# Battery_Chager_x3.net
KiCad netlist of a schematic drawn in Altium Designer
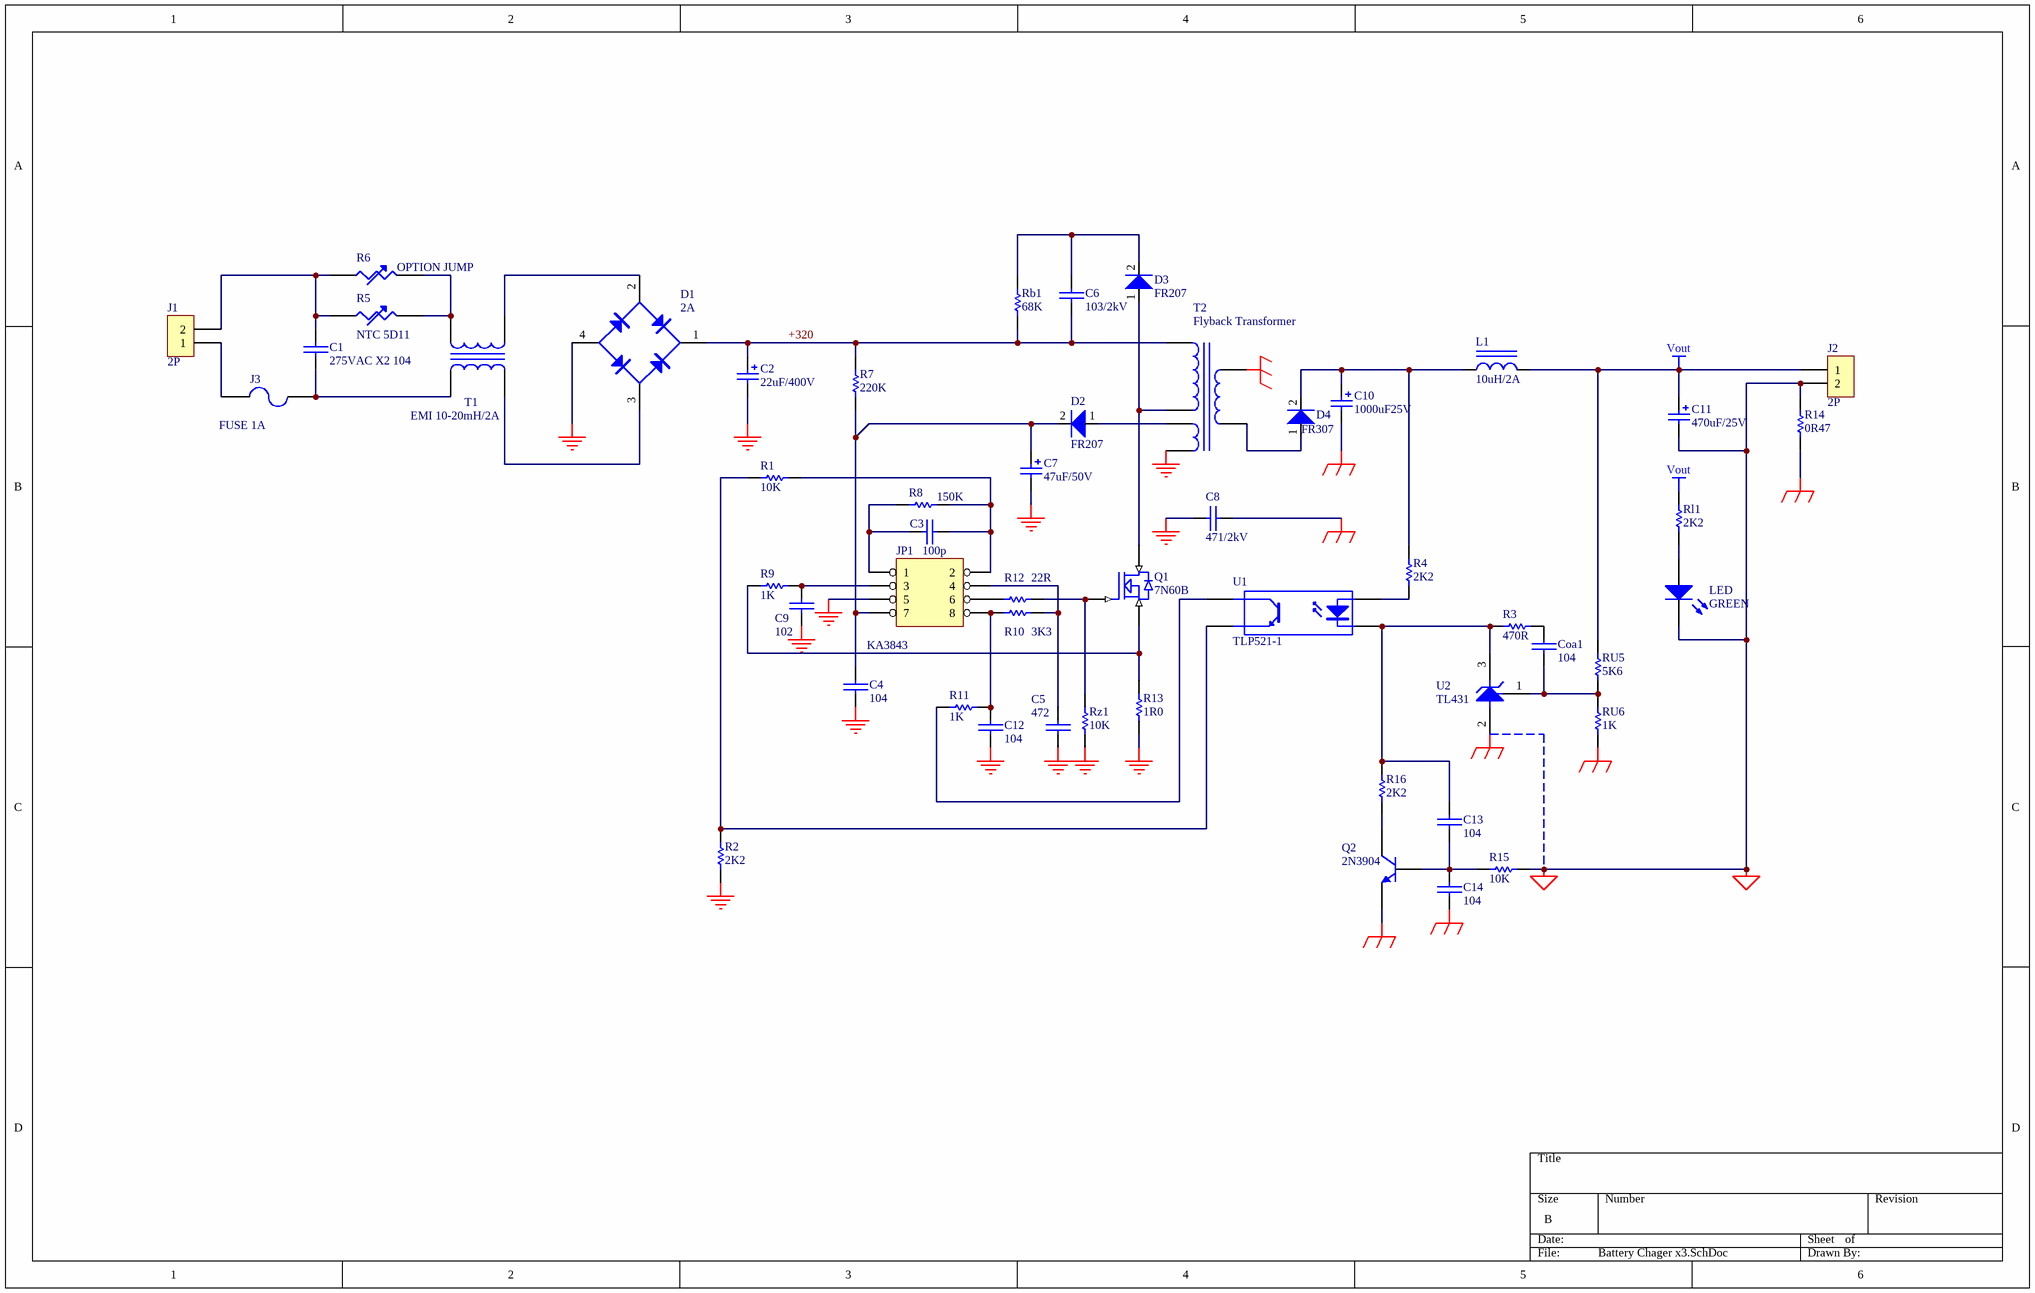
[diagram p0: Battery Chager x3.SchDoc]

(export (version "E")
  (design (tool "Eeschema 10.0.6"))
  (components
    (comp (ref "C1")
      (value "275VAC X2 104")
      (footprint "100N400v")
      (fields (field (name "Comment") "Tụ điện chân cắm275VAC X2 104"))
      (libsource (lib "DnsSchLib") (part "CAP"))
    )
    (comp (ref "C2")
      (value "22uF/400V")
      (footprint "1000u50v")
      (description "Polarized Capacitor (Radial)")
      (fields (field (name "Comment") "Tụ hóa chân cắm22uF/400V") (field (name "PUBLISHER") "*"))
      (libsource (lib "DnsSchLib") (part "Cap Pol1"))
    )
    (comp (ref "C3")
      (value "100p")
      (footprint "0805C")
      (fields (field (name "Comment") "Tụ điện dán 0805100p"))
      (libsource (lib "DnsSchLib") (part "CAP"))
    )
    (comp (ref "C4")
      (value "104")
      (footprint "0805C")
      (fields (field (name "Comment") "Tụ điện dán 0805104"))
      (libsource (lib "DnsSchLib") (part "CAP"))
    )
    (comp (ref "C5")
      (value "472")
      (footprint "104nho")
      (fields (field (name "Comment") "Tụ điện chân cắm472"))
      (libsource (lib "DnsSchLib") (part "CAP"))
    )
    (comp (ref "C6")
      (value "103/2kV")
      (footprint "10n1000v")
      (fields (field (name "Comment") "Tụ điện chân cắm103/2kV"))
      (libsource (lib "DnsSchLib") (part "CAP"))
    )
    (comp (ref "C7")
      (value "47uF/50V")
      (footprint "10u50V")
      (description "Polarized Capacitor (Radial)")
      (fields (field (name "Comment") "Tụ hóa chân cắm47uF/50V") (field (name "PUBLISHER") "*"))
      (libsource (lib "DnsSchLib") (part "Cap Pol1"))
    )
    (comp (ref "C8")
      (value "471/2kV")
      (footprint "10n1000v")
      (fields (field (name "Comment") "Tụ điện chân cắm471/2kV"))
      (libsource (lib "DnsSchLib") (part "CAP"))
    )
    (comp (ref "C9")
      (value "102")
      (footprint "0805C")
      (fields (field (name "Comment") "Tụ điện dán 0805102"))
      (libsource (lib "DnsSchLib") (part "CAP"))
    )
    (comp (ref "C10")
      (value "1000uF25V")
      (footprint "1000u16v")
      (description "Polarized Capacitor (Radial)")
      (fields (field (name "Comment") "Tụ hóa chân cắm1000uF25V") (field (name "PUBLISHER") "*"))
      (libsource (lib "DnsSchLib") (part "Cap Pol1"))
    )
    (comp (ref "C11")
      (value "470uF/25V")
      (footprint "1000u16v")
      (description "Polarized Capacitor (Radial)")
      (fields (field (name "Comment") "Tụ hóa chân cắm470uF/25V") (field (name "PUBLISHER") "*"))
      (libsource (lib "DnsSchLib") (part "Cap Pol1"))
    )
    (comp (ref "C12")
      (value "104")
      (footprint "0805C")
      (fields (field (name "Comment") "Tụ điện dán 0805104"))
      (libsource (lib "DnsSchLib") (part "CAP"))
    )
    (comp (ref "C13")
      (value "104")
      (footprint "0805C")
      (fields (field (name "Comment") "Tụ điện dán 0805104"))
      (libsource (lib "DnsSchLib") (part "CAP"))
    )
    (comp (ref "C14")
      (value "104")
      (footprint "0805C")
      (fields (field (name "Comment") "Tụ điện dán 0805104"))
      (libsource (lib "DnsSchLib") (part "CAP"))
    )
    (comp (ref "Coa1")
      (value "104")
      (footprint "0805C")
      (fields (field (name "Comment") "Tụ điện dán 0805104"))
      (libsource (lib "DnsSchLib") (part "CAP"))
    )
    (comp (ref "D1")
      (value "2A")
      (footprint "Cau2a")
      (description "Diode Bridge")
      (fields (field (name "Comment") "Cầu chỉnh lưu Diode dẹt, chân cắm2A"))
      (libsource (lib "DnsSchLib") (part "BRIDGE1"))
    )
    (comp (ref "D2")
      (value "FR207")
      (footprint "DIODE1A")
      (fields (field (name "Comment") "Diode xung chân cắm 2AFR207"))
      (libsource (lib "DnsSchLib") (part "DIODE"))
    )
    (comp (ref "D3")
      (value "FR207")
      (footprint "DIODE1A")
      (fields (field (name "Comment") "Diode xung chân cắm 2AFR207"))
      (libsource (lib "DnsSchLib") (part "DIODE"))
    )
    (comp (ref "D4")
      (value "FR307")
      (footprint "1N5408")
      (fields (field (name "Comment") "Diode xung chân cắm 3AFR307"))
      (libsource (lib "DnsSchLib") (part "DIODE"))
    )
    (comp (ref "J1")
      (value "2P")
      (footprint "jack2_nam")
      (fields (field (name "Comment") "Jump đực loại thẳng, 2.54mm2P"))
      (libsource (lib "DnsSchLib") (part "CON2"))
    )
    (comp (ref "J2")
      (value "2P")
      (footprint "jack2_nam")
      (fields (field (name "Comment") "Jump đực loại thẳng, 2.54mm2P"))
      (libsource (lib "") (part "CON2_1"))
    )
    (comp (ref "J3")
      (value "FUSE 1A")
      (footprint "R2W_DUNG")
      (description "Fuse")
      (fields (field (name "Comment") "Cầu chì 1A/275V"))
      (libsource (lib "*") (part "FUSE2"))
    )
    (comp (ref "JP1")
      (value "KA3843")
      (footprint "DIP8")
      (fields (field (name "Comment") "IC điều khiển nguồn AC-DC KA3843"))
      (libsource (lib "*") (part "HEADER 4X2"))
    )
    (comp (ref "L1")
      (value "10uH/2A")
      (footprint "330uH")
      (fields (field (name "Comment") "Cuộn cảm chân cắm lõi trụ10uH/2A"))
      (libsource (lib "DnsSchLib") (part "INDUCTORSMALL"))
    )
    (comp (ref "LED")
      (value "GREEN")
      (footprint "LED0805")
      (description "Typical INFRARED GaAs LED")
      (fields (field (name "Comment") "LED dán 0805GREEN") (field (name "PUBLISHER") "*"))
      (libsource (lib "DnsSchLib") (part "LED0"))
    )
    (comp (ref "Q1")
      (value "7N60B")
      (footprint "TO220TNB")
      (fields (field (name "Comment") "Transistor trường MOSFET N, chân cắm TO-2207N60B"))
      (libsource (lib "DnsSchLib") (part "MOSFET N"))
    )
    (comp (ref "Q2")
      (value "2N3904")
      (footprint "SOT23S")
      (description "NPN Bipolar Transistor")
      (fields
        (field (name "Comment") "Transistor BJT NPN, chân dán SOT-232N3904")
        (field (name "PUBLISHER") "*")
      )
      (libsource (lib "DnsSchLib") (part "NPN"))
    )
    (comp (ref "R1")
      (value "10K")
      (footprint "0805DD")
      (description "Semiconductor Resistor")
      (fields (field (name "Comment") "Điện trở dán 080510K") (field (name "PUBLISHER") "*"))
      (libsource (lib "DnsSchLib") (part "Res Semi"))
    )
    (comp (ref "R2")
      (value "2K2")
      (footprint "0805DD")
      (description "Semiconductor Resistor")
      (fields (field (name "Comment") "Điện trở dán 08052K2") (field (name "PUBLISHER") "*"))
      (libsource (lib "DnsSchLib") (part "Res Semi"))
    )
    (comp (ref "R3")
      (value "470R")
      (footprint "0805DD")
      (description "Semiconductor Resistor")
      (fields (field (name "Comment") "Điện trở dán 0805470R") (field (name "PUBLISHER") "*"))
      (libsource (lib "DnsSchLib") (part "Res Semi"))
    )
    (comp (ref "R4")
      (value "2K2")
      (footprint "0805DD")
      (description "Semiconductor Resistor")
      (fields (field (name "Comment") "Điện trở dán 08052K2") (field (name "PUBLISHER") "*"))
      (libsource (lib "DnsSchLib") (part "Res Semi"))
    )
    (comp (ref "R5")
      (value "NTC 5D11")
      (footprint "CSIP4")
      (fields (field (name "Comment") "Nhiệt điện trở âm NTC 5D11"))
      (libsource (lib "*") (part "RES3"))
    )
    (comp (ref "R6") (value "OPTION JUMP") (footprint "XPAD") (libsource (lib "*") (part "RES3")))
    (comp (ref "R7")
      (value "220K")
      (footprint "R2W_DUNG")
      (description "Semiconductor Resistor")
      (fields (field (name "Comment") "Điện trở chân cắm 2W220K") (field (name "PUBLISHER") "*"))
      (libsource (lib "DnsSchLib") (part "Res Semi"))
    )
    (comp (ref "R8")
      (value "150K")
      (footprint "0805DD")
      (description "Semiconductor Resistor")
      (fields (field (name "Comment") "Điện trở dán 0805150K") (field (name "PUBLISHER") "*"))
      (libsource (lib "DnsSchLib") (part "Res Semi"))
    )
    (comp (ref "R9")
      (value "1K")
      (footprint "0805DD")
      (description "Semiconductor Resistor")
      (fields (field (name "Comment") "Điện trở dán 08051K") (field (name "PUBLISHER") "*"))
      (libsource (lib "DnsSchLib") (part "Res Semi"))
    )
    (comp (ref "R10")
      (value "3K3")
      (footprint "0805DD")
      (description "Semiconductor Resistor")
      (fields (field (name "Comment") "Điện trở dán 08053K3") (field (name "PUBLISHER") "*"))
      (libsource (lib "DnsSchLib") (part "Res Semi"))
    )
    (comp (ref "R11")
      (value "1K")
      (footprint "0805DD")
      (description "Semiconductor Resistor")
      (fields (field (name "Comment") "Điện trở dán 08051K") (field (name "PUBLISHER") "*"))
      (libsource (lib "DnsSchLib") (part "Res Semi"))
    )
    (comp (ref "R12")
      (value "22R")
      (footprint "0805DD")
      (description "Semiconductor Resistor")
      (fields (field (name "Comment") "Điện trở dán 080522R") (field (name "PUBLISHER") "*"))
      (libsource (lib "DnsSchLib") (part "Res Semi"))
    )
    (comp (ref "R13")
      (value "1R0")
      (footprint "R2WDUNG")
      (description "Semiconductor Resistor")
      (fields (field (name "Comment") "Điện trở chân cắm 2W1R0") (field (name "PUBLISHER") "*"))
      (libsource (lib "DnsSchLib") (part "Res Semi"))
    )
    (comp (ref "R14")
      (value "0R47")
      (footprint "R2WDUNG")
      (description "Semiconductor Resistor")
      (fields (field (name "Comment") "Điện trở chân cắm 2W0R47") (field (name "PUBLISHER") "*"))
      (libsource (lib "DnsSchLib") (part "Res Semi"))
    )
    (comp (ref "R15")
      (value "10K")
      (footprint "0805DD")
      (description "Semiconductor Resistor")
      (fields (field (name "Comment") "Điện trở dán 080510K") (field (name "PUBLISHER") "*"))
      (libsource (lib "DnsSchLib") (part "Res Semi"))
    )
    (comp (ref "R16")
      (value "2K2")
      (footprint "0805DD")
      (description "Semiconductor Resistor")
      (fields (field (name "Comment") "Điện trở dán 08052K2") (field (name "PUBLISHER") "*"))
      (libsource (lib "DnsSchLib") (part "Res Semi"))
    )
    (comp (ref "Rb1")
      (value "68K")
      (footprint "AXIAL0.4")
      (description "Semiconductor Resistor")
      (fields (field (name "Comment") "Điện trở chân cắm 1W68K") (field (name "PUBLISHER") "*"))
      (libsource (lib "DnsSchLib") (part "Res Semi"))
    )
    (comp (ref "Rl1")
      (value "2K2")
      (footprint "0805DD")
      (description "Semiconductor Resistor")
      (fields (field (name "Comment") "Điện trở dán 08052K2") (field (name "PUBLISHER") "*"))
      (libsource (lib "DnsSchLib") (part "Res Semi"))
    )
    (comp (ref "RU5")
      (value "5K6")
      (footprint "0805DD")
      (description "Semiconductor Resistor")
      (fields (field (name "Comment") "Điện trở dán 08055K6") (field (name "PUBLISHER") "*"))
      (libsource (lib "DnsSchLib") (part "Res Semi"))
    )
    (comp (ref "RU6")
      (value "1K")
      (footprint "0805DD")
      (description "Semiconductor Resistor")
      (fields (field (name "Comment") "Điện trở dán 08051K") (field (name "PUBLISHER") "*"))
      (libsource (lib "DnsSchLib") (part "Res Semi"))
    )
    (comp (ref "Rz1")
      (value "10K")
      (footprint "0805DD")
      (description "Semiconductor Resistor")
      (fields (field (name "Comment") "Điện trở dán 080510K") (field (name "PUBLISHER") "*"))
      (libsource (lib "DnsSchLib") (part "Res Semi"))
    )
    (comp (ref "T1")
      (value "EMI 10-20mH/2A")
      (footprint "EMI_Filter")
      (fields (field (name "Comment") "Cuộn cảm lọc đầu vào EMI Filter 10-20mH/2A"))
      (libsource (lib "*") (part "TRANS1"))
    )
    (comp (ref "T2")
      (value "Flyback Transformer")
      (footprint "Trans6c")
      (fields (field (name "Comment") "Biến áp xung Flyback"))
      (libsource (lib "*") (part "TRANS6"))
    )
    (comp (ref "U1")
      (value "TLP521-1")
      (footprint "TLP521_1")
      (description "Optoisolator")
      (fields (field (name "Comment") "Cách ly quang chân cắmTLP521-1"))
      (libsource (lib "DnsSchLib") (part "OPTOISO1"))
    )
    (comp (ref "U2")
      (value "TL431")
      (footprint "TO92_431")
      (description "Adjustable Precision Shunt Regulator")
      (fields (field (name "Comment") "IC điện áp chuẩn, chân cắm TO92TL431"))
      (libsource (lib "DnsSchLib") (part "TL431"))
    )
  )
  (nets
    (net (code "1") (name "/+320") (class "Default")
      (node (ref "C2") (pin "1") (pinfunction "1_1") (pintype "passive"))
      (node (ref "C6") (pin "2") (pinfunction "2_2") (pintype "passive"))
      (node (ref "D1") (pin "1") (pinfunction "V+_1") (pintype "passive"))
      (node (ref "R7") (pin "2") (pinfunction "2_2") (pintype "passive"))
      (node (ref "Rb1") (pin "2") (pinfunction "2_2") (pintype "passive"))
      (node (ref "T2") (pin "1") (pinfunction "1_1") (pintype "passive"))
    )
    (net (code "2") (name "EARTH") (class "Default")
      (node (ref "C10") (pin "2") (pinfunction "2_2") (pintype "passive"))
      (node (ref "C14") (pin "2") (pinfunction "2_2") (pintype "passive"))
      (node (ref "C8") (pin "2") (pinfunction "2_2") (pintype "passive"))
      (node (ref "Q2") (pin "3") (pinfunction "E_3") (pintype "passive"))
      (node (ref "R14") (pin "1") (pinfunction "1_1") (pintype "passive"))
      (node (ref "RU6") (pin "2") (pinfunction "2_2") (pintype "passive"))
      (node (ref "T2") (pin "5") (pinfunction "5_5") (pintype "passive"))
      (node (ref "U2") (pin "2") (pinfunction "A_2") (pintype "passive"))
    )
    (net (code "3") (name "EARTH2") (class "Default")
      (node (ref "C11") (pin "2") (pinfunction "2_2") (pintype "passive"))
      (node (ref "J2") (pin "2") (pinfunction "2_2") (pintype "passive"))
      (node (ref "LED") (pin "2") (pinfunction "K_2") (pintype "passive"))
      (node (ref "R14") (pin "2") (pinfunction "2_2") (pintype "passive"))
      (node (ref "R15") (pin "2") (pinfunction "2_2") (pintype "passive"))
    )
    (net (code "4") (name "GND") (class "Default")
      (node (ref "C12") (pin "2") (pinfunction "2_2") (pintype "passive"))
      (node (ref "C2") (pin "2") (pinfunction "2_2") (pintype "passive"))
      (node (ref "C4") (pin "2") (pinfunction "2_2") (pintype "passive"))
      (node (ref "C5") (pin "1") (pinfunction "1_1") (pintype "passive"))
      (node (ref "C7") (pin "2") (pinfunction "2_2") (pintype "passive"))
      (node (ref "C8") (pin "1") (pinfunction "1_1") (pintype "passive"))
      (node (ref "C9") (pin "2") (pinfunction "2_2") (pintype "passive"))
      (node (ref "D1") (pin "4") (pinfunction "V-_4") (pintype "passive"))
      (node (ref "JP1") (pin "5") (pinfunction "5_5") (pintype "passive"))
      (node (ref "R13") (pin "2") (pinfunction "2_2") (pintype "passive"))
      (node (ref "R2") (pin "2") (pinfunction "2_2") (pintype "passive"))
      (node (ref "Rz1") (pin "2") (pinfunction "2_2") (pintype "passive"))
      (node (ref "T2") (pin "4") (pinfunction "4_4") (pintype "passive"))
    )
    (net (code "5") (name "Net-(C1-Pad1)") (class "Default")
      (node (ref "C1") (pin "1") (pinfunction "1_1") (pintype "passive"))
      (node (ref "J3") (pin "2") (pinfunction "2_2") (pintype "passive"))
      (node (ref "T1") (pin "1") (pinfunction "1_1") (pintype "passive"))
    )
    (net (code "6") (name "Net-(C1-Pad2)") (class "Default")
      (node (ref "C1") (pin "2") (pinfunction "2_2") (pintype "passive"))
      (node (ref "J1") (pin "2") (pinfunction "2_2") (pintype "passive"))
      (node (ref "R5") (pin "1") (pinfunction "1_1") (pintype "passive"))
      (node (ref "R6") (pin "1") (pinfunction "1_1") (pintype "passive"))
    )
    (net (code "7") (name "Net-(C3-Pad1)") (class "Default")
      (node (ref "C3") (pin "1") (pinfunction "1_1") (pintype "passive"))
      (node (ref "JP1") (pin "1") (pinfunction "1_1") (pintype "passive"))
      (node (ref "R8") (pin "1") (pinfunction "1_1") (pintype "passive"))
    )
    (net (code "8") (name "Net-(C3-Pad2)") (class "Default")
      (node (ref "C3") (pin "2") (pinfunction "2_2") (pintype "passive"))
      (node (ref "JP1") (pin "2") (pinfunction "2_2") (pintype "passive"))
      (node (ref "R1") (pin "2") (pinfunction "2_2") (pintype "passive"))
      (node (ref "R8") (pin "2") (pinfunction "2_2") (pintype "passive"))
    )
    (net (code "9") (name "Net-(C5-Pad2)") (class "Default")
      (node (ref "C5") (pin "2") (pinfunction "2_2") (pintype "passive"))
      (node (ref "JP1") (pin "4") (pinfunction "4_4") (pintype "passive"))
      (node (ref "R10") (pin "2") (pinfunction "2_2") (pintype "passive"))
    )
    (net (code "10") (name "Net-(C9-Pad1)") (class "Default")
      (node (ref "C9") (pin "1") (pinfunction "1_1") (pintype "passive"))
      (node (ref "JP1") (pin "3") (pinfunction "3_3") (pintype "passive"))
      (node (ref "R9") (pin "1") (pinfunction "1_1") (pintype "passive"))
    )
    (net (code "11") (name "Net-(C12-Pad1)") (class "Default")
      (node (ref "C12") (pin "1") (pinfunction "1_1") (pintype "passive"))
      (node (ref "JP1") (pin "8") (pinfunction "8_8") (pintype "passive"))
      (node (ref "R10") (pin "1") (pinfunction "1_1") (pintype "passive"))
      (node (ref "R11") (pin "1") (pinfunction "1_1") (pintype "passive"))
    )
    (net (code "12") (name "Net-(Coa1-Pad1)") (class "Default")
      (node (ref "Coa1") (pin "1") (pinfunction "1_1") (pintype "passive"))
      (node (ref "R3") (pin "1") (pinfunction "1_1") (pintype "passive"))
    )
    (net (code "13") (name "Net-(D1-AC-Pad2)") (class "Default")
      (node (ref "D1") (pin "2") (pinfunction "AC_2") (pintype "passive"))
      (node (ref "T1") (pin "4") (pinfunction "4_4") (pintype "passive"))
    )
    (net (code "14") (name "Net-(D1-AC-Pad3)") (class "Default")
      (node (ref "D1") (pin "3") (pinfunction "AC_3") (pintype "passive"))
      (node (ref "T1") (pin "3") (pinfunction "3_3") (pintype "passive"))
    )
    (net (code "15") (name "Net-(D2-A)") (class "Default")
      (node (ref "D2") (pin "1") (pinfunction "A_1") (pintype "passive"))
      (node (ref "T2") (pin "3") (pinfunction "3_3") (pintype "passive"))
    )
    (net (code "16") (name "Net-(D2-K)") (class "Default")
      (node (ref "C4") (pin "1") (pinfunction "1_1") (pintype "passive"))
      (node (ref "C7") (pin "1") (pinfunction "1_1") (pintype "passive"))
      (node (ref "D2") (pin "2") (pinfunction "K_2") (pintype "passive"))
      (node (ref "JP1") (pin "7") (pinfunction "7_7") (pintype "passive"))
      (node (ref "R7") (pin "1") (pinfunction "1_1") (pintype "passive"))
    )
    (net (code "17") (name "Net-(D3-A)") (class "Default")
      (node (ref "D3") (pin "1") (pinfunction "A_1") (pintype "passive"))
      (node (ref "Q1") (pin "2") (pinfunction "D_2") (pintype "input"))
      (node (ref "T2") (pin "2") (pinfunction "2_2") (pintype "passive"))
    )
    (net (code "18") (name "Net-(D3-K)") (class "Default")
      (node (ref "C6") (pin "1") (pinfunction "1_1") (pintype "passive"))
      (node (ref "D3") (pin "2") (pinfunction "K_2") (pintype "passive"))
      (node (ref "Rb1") (pin "1") (pinfunction "1_1") (pintype "passive"))
    )
    (net (code "19") (name "Net-(D4-A)") (class "Default")
      (node (ref "D4") (pin "1") (pinfunction "A_1") (pintype "passive"))
      (node (ref "T2") (pin "6") (pinfunction "6_6") (pintype "passive"))
    )
    (net (code "20") (name "Net-(D4-K)") (class "Default")
      (node (ref "C10") (pin "1") (pinfunction "1_1") (pintype "passive"))
      (node (ref "D4") (pin "2") (pinfunction "K_2") (pintype "passive"))
      (node (ref "L1") (pin "1") (pinfunction "1_1") (pintype "passive"))
      (node (ref "R4") (pin "2") (pinfunction "2_2") (pintype "passive"))
    )
    (net (code "21") (name "Net-(J1-Pad1)") (class "Default")
      (node (ref "J1") (pin "1") (pinfunction "1_1") (pintype "passive"))
      (node (ref "J3") (pin "1") (pinfunction "1_1") (pintype "passive"))
    )
    (net (code "22") (name "Net-(JP1-Pad6)") (class "Default")
      (node (ref "JP1") (pin "6") (pinfunction "6_6") (pintype "passive"))
      (node (ref "R12") (pin "1") (pinfunction "1_1") (pintype "passive"))
    )
    (net (code "23") (name "Net-(LED-A)") (class "Default")
      (node (ref "LED") (pin "1") (pinfunction "A_1") (pintype "passive"))
      (node (ref "Rl1") (pin "2") (pinfunction "2_2") (pintype "passive"))
    )
    (net (code "24") (name "Net-(Q1-G)") (class "Default")
      (node (ref "Q1") (pin "1") (pinfunction "G_1") (pintype "input"))
      (node (ref "R12") (pin "2") (pinfunction "2_2") (pintype "passive"))
      (node (ref "Rz1") (pin "1") (pinfunction "1_1") (pintype "passive"))
    )
    (net (code "25") (name "Net-(Q1-S)") (class "Default")
      (node (ref "Q1") (pin "3") (pinfunction "S_3") (pintype "input"))
      (node (ref "R13") (pin "1") (pinfunction "1_1") (pintype "passive"))
      (node (ref "R9") (pin "2") (pinfunction "2_2") (pintype "passive"))
    )
    (net (code "26") (name "Net-(Q2-B)") (class "Default")
      (node (ref "C13") (pin "1") (pinfunction "1_1") (pintype "passive"))
      (node (ref "C14") (pin "1") (pinfunction "1_1") (pintype "passive"))
      (node (ref "Q2") (pin "1") (pinfunction "B_1") (pintype "passive"))
      (node (ref "R15") (pin "1") (pinfunction "1_1") (pintype "passive"))
    )
    (net (code "27") (name "Net-(Q2-C)") (class "Default")
      (node (ref "Q2") (pin "2") (pinfunction "C_2") (pintype "passive"))
      (node (ref "R16") (pin "1") (pinfunction "1_1") (pintype "passive"))
    )
    (net (code "28") (name "Net-(R5-Pad2)") (class "Default")
      (node (ref "R5") (pin "2") (pinfunction "2_2") (pintype "passive"))
      (node (ref "R6") (pin "2") (pinfunction "2_2") (pintype "passive"))
      (node (ref "T1") (pin "2") (pinfunction "2_2") (pintype "passive"))
    )
    (net (code "29") (name "Net-(U1-A)") (class "Default")
      (node (ref "R4") (pin "1") (pinfunction "1_1") (pintype "passive"))
      (node (ref "U1") (pin "1") (pinfunction "A_1") (pintype "passive"))
    )
    (net (code "30") (name "Net-(U1-C)") (class "Default")
      (node (ref "R1") (pin "1") (pinfunction "1_1") (pintype "passive"))
      (node (ref "R2") (pin "1") (pinfunction "1_1") (pintype "passive"))
      (node (ref "U1") (pin "3") (pinfunction "C_3") (pintype "passive"))
    )
    (net (code "31") (name "Net-(U1-E)") (class "Default")
      (node (ref "R11") (pin "2") (pinfunction "2_2") (pintype "passive"))
      (node (ref "U1") (pin "4") (pinfunction "E_4") (pintype "passive"))
    )
    (net (code "32") (name "Net-(U1-K)") (class "Default")
      (node (ref "C13") (pin "2") (pinfunction "2_2") (pintype "passive"))
      (node (ref "R16") (pin "2") (pinfunction "2_2") (pintype "passive"))
      (node (ref "R3") (pin "2") (pinfunction "2_2") (pintype "passive"))
      (node (ref "U1") (pin "2") (pinfunction "K_2") (pintype "passive"))
      (node (ref "U2") (pin "3") (pinfunction "K_3") (pintype "passive"))
    )
    (net (code "33") (name "Net-(U2-R)") (class "Default")
      (node (ref "Coa1") (pin "2") (pinfunction "2_2") (pintype "passive"))
      (node (ref "RU5") (pin "2") (pinfunction "2_2") (pintype "passive"))
      (node (ref "RU6") (pin "1") (pinfunction "1_1") (pintype "passive"))
      (node (ref "U2") (pin "1") (pinfunction "R_1") (pintype "passive"))
    )
    (net (code "34") (name "Vout") (class "Default")
      (node (ref "C11") (pin "1") (pinfunction "1_1") (pintype "passive"))
      (node (ref "J2") (pin "1") (pinfunction "1_1") (pintype "passive"))
      (node (ref "L1") (pin "2") (pinfunction "2_2") (pintype "passive"))
      (node (ref "RU5") (pin "1") (pinfunction "1_1") (pintype "passive"))
      (node (ref "Rl1") (pin "1") (pinfunction "1_1") (pintype "passive"))
    )
  )
)
